# Supersensor.net
KiCad netlist of a schematic drawn in Altium Designer
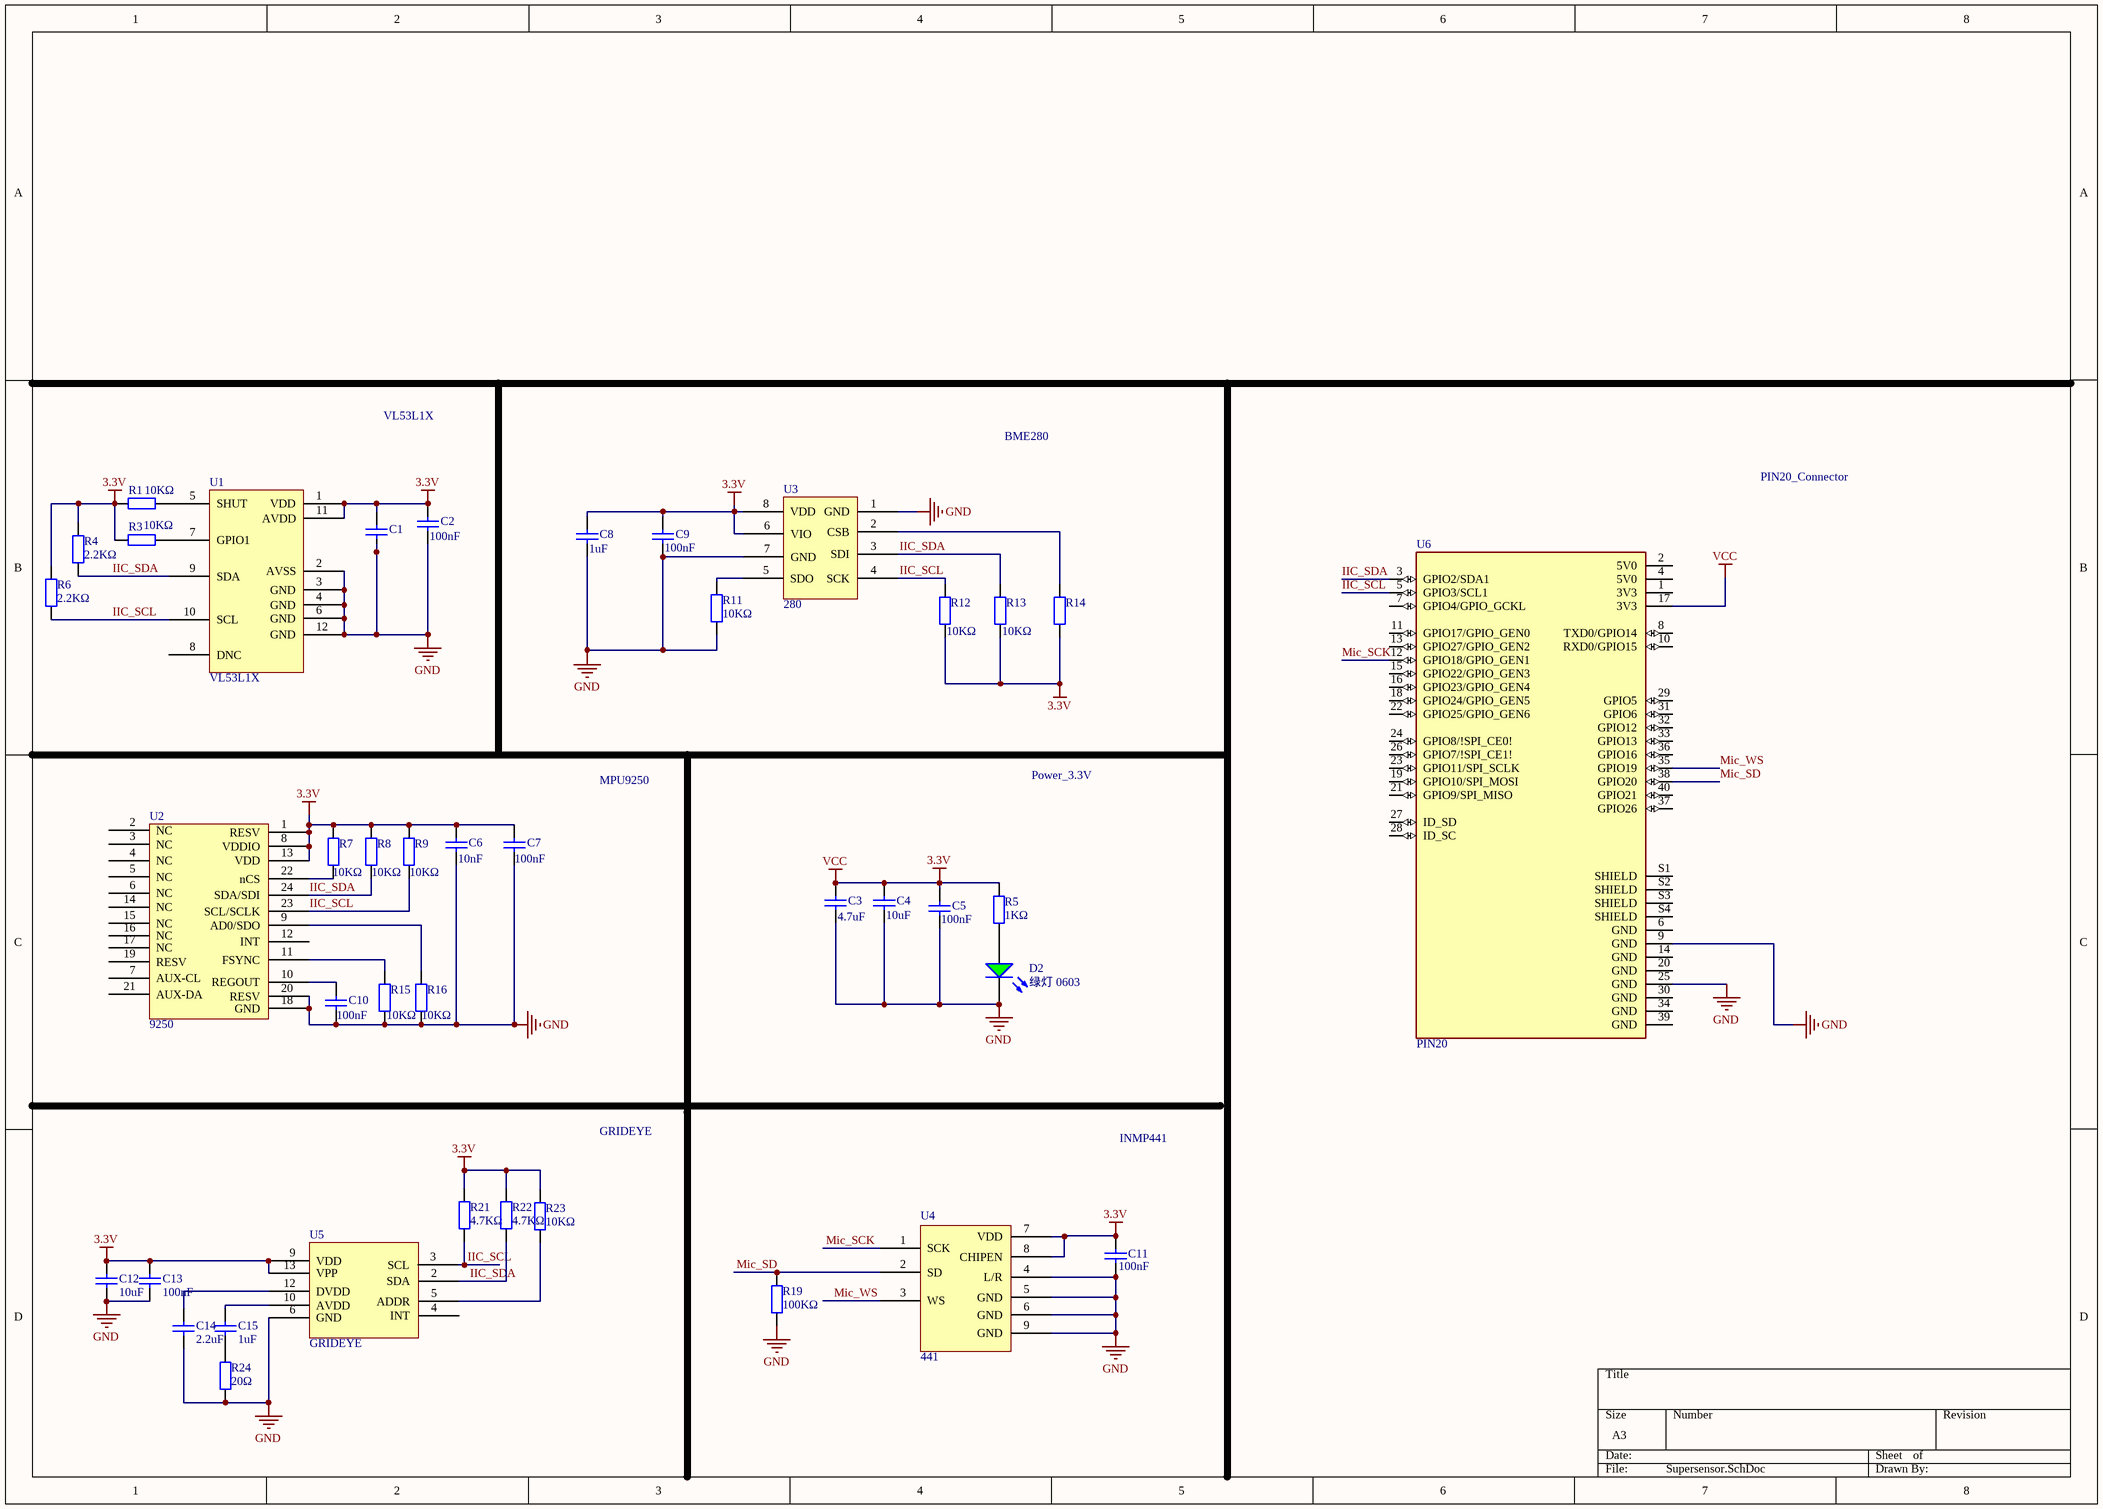
[diagram p0: Supersensor.SchDoc]

(export (version "E")
  (design (tool "Eeschema 10.0.6"))
  (components
    (comp (ref "C1")
      (value "~")
      (footprint "0603_C")
      (description "贴片电容")
      (libsource (lib "Miscellaneous Devices LC") (part "0603 4.7uF (475) 10% 16V"))
    )
    (comp (ref "C2")
      (value "100nF")
      (footprint "0603_C")
      (description "贴片电容")
      (libsource (lib "supersensor") (part "0603 100nF (104) 10% 50V"))
    )
    (comp (ref "C3")
      (value "4.7uF")
      (footprint "0603_C")
      (description "贴片电容")
      (libsource (lib "supersensor") (part "0603 4.7uF (475) 10% 16V"))
    )
    (comp (ref "C4")
      (value "10uF")
      (footprint "0603_C")
      (description "贴片电容")
      (libsource (lib "supersensor") (part "0603 10uF (106) 10% 10V"))
    )
    (comp (ref "C5")
      (value "100nF")
      (footprint "0603_C")
      (description "贴片电容")
      (libsource (lib "supersensor") (part "0603 100nF (104) 10% 50V"))
    )
    (comp (ref "C6")
      (value "10nF")
      (footprint "0603_C")
      (description "贴片电容")
      (libsource (lib "supersensor") (part "0603 10nF (103) 10% 50V"))
    )
    (comp (ref "C7")
      (value "100nF")
      (footprint "0603_C")
      (description "贴片电容")
      (libsource (lib "supersensor") (part "0603 100nF (104) 10% 50V"))
    )
    (comp (ref "C8")
      (value "1uF")
      (footprint "0603_C")
      (description "贴片电容")
      (libsource (lib "supersensor") (part "0603 1uF (105) 10% 50V"))
    )
    (comp (ref "C9")
      (value "100nF")
      (footprint "0603_C")
      (description "贴片电容")
      (libsource (lib "supersensor") (part "0603 100nF (104) 10% 50V"))
    )
    (comp (ref "C10")
      (value "100nF")
      (footprint "0603_C")
      (description "贴片电容")
      (libsource (lib "supersensor") (part "0603 100nF (104) 10% 50V"))
    )
    (comp (ref "C11")
      (value "100nF")
      (footprint "0603_C")
      (description "贴片电容")
      (libsource (lib "supersensor") (part "0603 100nF (104) 10% 50V"))
    )
    (comp (ref "C12")
      (value "10uF")
      (footprint "0603_C")
      (description "贴片电容")
      (libsource (lib "supersensor") (part "0603 10uF (106) 10% 10V"))
    )
    (comp (ref "C13")
      (value "100nF")
      (footprint "0603_C")
      (description "贴片电容")
      (libsource (lib "supersensor") (part "0603 100nF (104) 10% 50V"))
    )
    (comp (ref "C14")
      (value "2.2uF")
      (footprint "0603_C")
      (description "贴片电容")
      (libsource (lib "supersensor") (part "0603 2.2uF (225) 10% 16V"))
    )
    (comp (ref "C15")
      (value "1uF")
      (footprint "0603_C")
      (description "贴片电容")
      (libsource (lib "supersensor") (part "0603 1uF (105) 10% 50V"))
    )
    (comp (ref "D2")
      (value "绿灯 0603")
      (footprint "0603_LED_S1")
      (description "发光二极管")
      (libsource (lib "supersensor") (part "0603 绿灯"))
    )
    (comp (ref "R1")
      (value "10KΩ")
      (footprint "0603_R")
      (description "贴片电阻")
      (libsource (lib "") (part "0603 10KΩ (1002) 1%_1"))
    )
    (comp (ref "R3")
      (value "10KΩ")
      (footprint "0603_R")
      (description "贴片电阻")
      (libsource (lib "") (part "0603 10KΩ (1002) 1%_1"))
    )
    (comp (ref "R4")
      (value "2.2KΩ")
      (footprint "0603_R")
      (description "贴片电阻")
      (libsource (lib "supersensor") (part "0603 2.2KΩ (2201) 1%"))
    )
    (comp (ref "R5")
      (value "1KΩ")
      (footprint "0603_R")
      (description "贴片电阻")
      (libsource (lib "supersensor") (part "0603 1KΩ (1001) 1%"))
    )
    (comp (ref "R6")
      (value "2.2KΩ")
      (footprint "0603_R")
      (description "贴片电阻")
      (libsource (lib "supersensor") (part "0603 2.2KΩ (2201) 1%"))
    )
    (comp (ref "R7")
      (value "10KΩ")
      (footprint "0603_R")
      (description "贴片电阻")
      (libsource (lib "supersensor") (part "0603 10KΩ (1002) 1%"))
    )
    (comp (ref "R8")
      (value "10KΩ")
      (footprint "0603_R")
      (description "贴片电阻")
      (libsource (lib "supersensor") (part "0603 10KΩ (1002) 1%"))
    )
    (comp (ref "R9")
      (value "10KΩ")
      (footprint "0603_R")
      (description "贴片电阻")
      (libsource (lib "supersensor") (part "0603 10KΩ (1002) 1%"))
    )
    (comp (ref "R11")
      (value "10KΩ")
      (footprint "0603_R")
      (description "贴片电阻")
      (libsource (lib "supersensor") (part "0603 10KΩ (1002) 1%"))
    )
    (comp (ref "R12")
      (value "10KΩ")
      (footprint "0603_R")
      (description "贴片电阻")
      (libsource (lib "supersensor") (part "0603 10KΩ (1002) 1%"))
    )
    (comp (ref "R13")
      (value "10KΩ")
      (footprint "0603_R")
      (description "贴片电阻")
      (libsource (lib "supersensor") (part "0603 10KΩ (1002) 1%"))
    )
    (comp (ref "R14")
      (value "~")
      (footprint "0603_R")
      (description "贴片电阻")
      (libsource (lib "Miscellaneous Devices LC") (part "0603 10KΩ (1002) 1%"))
    )
    (comp (ref "R15")
      (value "10KΩ")
      (footprint "0603_R")
      (description "贴片电阻")
      (libsource (lib "supersensor") (part "0603 10KΩ (1002) 1%"))
    )
    (comp (ref "R16")
      (value "10KΩ")
      (footprint "0603_R")
      (description "贴片电阻")
      (libsource (lib "supersensor") (part "0603 10KΩ (1002) 1%"))
    )
    (comp (ref "R19")
      (value "100KΩ")
      (footprint "0603_R")
      (description "贴片电阻")
      (libsource (lib "supersensor") (part "0603 100KΩ (1003) 1%"))
    )
    (comp (ref "R21")
      (value "4.7KΩ")
      (footprint "0603_R")
      (description "贴片电阻")
      (libsource (lib "supersensor") (part "0603 4.7KΩ (4701) 1%"))
    )
    (comp (ref "R22")
      (value "4.7KΩ")
      (footprint "0603_R")
      (description "贴片电阻")
      (libsource (lib "supersensor") (part "0603 4.7KΩ (4701) 1%"))
    )
    (comp (ref "R23")
      (value "10KΩ")
      (footprint "0603_R")
      (description "贴片电阻")
      (libsource (lib "supersensor") (part "0603 10KΩ (1002) 1%"))
    )
    (comp (ref "R24")
      (value "20Ω")
      (footprint "0603_R")
      (description "贴片电阻")
      (libsource (lib "supersensor") (part "0603 20Ω (20R0) 1%"))
    )
    (comp (ref "U1")
      (value "VL53L1X")
      (footprint "VL53L1X")
      (description "IC")
      (libsource (lib "supersensor") (part "VL53L1X"))
    )
    (comp (ref "U2")
      (value "9250")
      (footprint "MPU9250")
      (description "IC")
      (libsource (lib "supersensor") (part "MPU9250"))
    )
    (comp (ref "U3")
      (value "280")
      (footprint "BME280")
      (description "IC")
      (libsource (lib "supersensor") (part "BME280"))
    )
    (comp (ref "U4")
      (value "441")
      (footprint "INMP441")
      (description "IC")
      (libsource (lib "supersensor") (part "INMP441"))
    )
    (comp (ref "U5")
      (value "GRIDEYE")
      (footprint "AMG8833")
      (description "IC")
      (libsource (lib "supersensor") (part "GRIDEYE"))
    )
    (comp (ref "U6")
      (value "PIN20")
      (footprint "PIN20")
      (description "BCM2837B0 Raspberry Pi 3 Model B+ - ARMÂ® CortexÂ®-A53, VideoCore MPU Embedded Evaluation Board")
      (fields (field (name "MP") "RASPBERRY PI 3 MODEL B+") (field (name "MF") "Raspberry Pi"))
      (libsource (lib "supersensor") (part "PIN20"))
    )
  )
  (nets
    (net (code "1") (name "/IIC_SCL") (class "Default")
      (node (ref "R12") (pin "2") (pinfunction "2_2") (pintype "passive"))
      (node (ref "R21") (pin "1") (pinfunction "1_1") (pintype "passive"))
      (node (ref "R6") (pin "2") (pinfunction "2_2") (pintype "passive"))
      (node (ref "R9") (pin "1") (pinfunction "1_1") (pintype "passive"))
      (node (ref "U1") (pin "10") (pinfunction "SCL_10") (pintype "passive"))
      (node (ref "U2") (pin "23") (pinfunction "SCL/SCLK_23") (pintype "passive"))
      (node (ref "U3") (pin "4") (pinfunction "SCK_4") (pintype "passive"))
      (node (ref "U5") (pin "3") (pinfunction "SCL_3") (pintype "passive"))
      (node (ref "U6") (pin "5") (pinfunction "GPIO3/SCL1_5") (pintype "bidirectional"))
    )
    (net (code "2") (name "/IIC_SDA") (class "Default")
      (node (ref "R13") (pin "2") (pinfunction "2_2") (pintype "passive"))
      (node (ref "R22") (pin "1") (pinfunction "1_1") (pintype "passive"))
      (node (ref "R4") (pin "2") (pinfunction "2_2") (pintype "passive"))
      (node (ref "R8") (pin "1") (pinfunction "1_1") (pintype "passive"))
      (node (ref "U1") (pin "9") (pinfunction "SDA_9") (pintype "passive"))
      (node (ref "U2") (pin "24") (pinfunction "SDA/SDI_24") (pintype "passive"))
      (node (ref "U3") (pin "3") (pinfunction "SDI_3") (pintype "passive"))
      (node (ref "U5") (pin "2") (pinfunction "SDA_2") (pintype "passive"))
      (node (ref "U6") (pin "3") (pinfunction "GPIO2/SDA1_3") (pintype "bidirectional"))
    )
    (net (code "3") (name "/Mic_SCK") (class "Default")
      (node (ref "U4") (pin "1") (pinfunction "SCK_1") (pintype "passive"))
      (node (ref "U6") (pin "12") (pinfunction "GPIO18/GPIO_GEN1_12") (pintype "bidirectional"))
    )
    (net (code "4") (name "/Mic_SD") (class "Default")
      (node (ref "R19") (pin "2") (pinfunction "2_2") (pintype "passive"))
      (node (ref "U4") (pin "2") (pinfunction "SD_2") (pintype "passive"))
      (node (ref "U6") (pin "38") (pinfunction "GPIO20_38") (pintype "bidirectional"))
    )
    (net (code "5") (name "/Mic_WS") (class "Default")
      (node (ref "U4") (pin "3") (pinfunction "WS_3") (pintype "passive"))
      (node (ref "U6") (pin "35") (pinfunction "GPIO19_35") (pintype "bidirectional"))
    )
    (net (code "6") (name "3.3V") (class "Default")
      (node (ref "C1") (pin "2") (pinfunction "2_2") (pintype "passive"))
      (node (ref "C11") (pin "2") (pinfunction "2_2") (pintype "passive"))
      (node (ref "C12") (pin "2") (pinfunction "2_2") (pintype "passive"))
      (node (ref "C13") (pin "2") (pinfunction "2_2") (pintype "passive"))
      (node (ref "C2") (pin "2") (pinfunction "2_2") (pintype "passive"))
      (node (ref "C3") (pin "2") (pinfunction "2_2") (pintype "passive"))
      (node (ref "C4") (pin "2") (pinfunction "2_2") (pintype "passive"))
      (node (ref "C5") (pin "2") (pinfunction "2_2") (pintype "passive"))
      (node (ref "C6") (pin "2") (pinfunction "2_2") (pintype "passive"))
      (node (ref "C7") (pin "2") (pinfunction "2_2") (pintype "passive"))
      (node (ref "C8") (pin "2") (pinfunction "2_2") (pintype "passive"))
      (node (ref "C9") (pin "2") (pinfunction "2_2") (pintype "passive"))
      (node (ref "R1") (pin "1") (pinfunction "1_1") (pintype "passive"))
      (node (ref "R12") (pin "1") (pinfunction "1_1") (pintype "passive"))
      (node (ref "R13") (pin "1") (pinfunction "1_1") (pintype "passive"))
      (node (ref "R14") (pin "1") (pinfunction "1_1") (pintype "passive"))
      (node (ref "R21") (pin "2") (pinfunction "2_2") (pintype "passive"))
      (node (ref "R22") (pin "2") (pinfunction "2_2") (pintype "passive"))
      (node (ref "R23") (pin "2") (pinfunction "2_2") (pintype "passive"))
      (node (ref "R3") (pin "1") (pinfunction "1_1") (pintype "passive"))
      (node (ref "R4") (pin "1") (pinfunction "1_1") (pintype "passive"))
      (node (ref "R5") (pin "2") (pinfunction "2_2") (pintype "passive"))
      (node (ref "R6") (pin "1") (pinfunction "1_1") (pintype "passive"))
      (node (ref "R7") (pin "2") (pinfunction "2_2") (pintype "passive"))
      (node (ref "R8") (pin "2") (pinfunction "2_2") (pintype "passive"))
      (node (ref "R9") (pin "2") (pinfunction "2_2") (pintype "passive"))
      (node (ref "U1") (pin "1") (pinfunction "VDD_1") (pintype "power_in"))
      (node (ref "U1") (pin "11") (pinfunction "AVDD_11") (pintype "passive"))
      (node (ref "U2") (pin "1") (pinfunction "RESV_1") (pintype "passive"))
      (node (ref "U2") (pin "13") (pinfunction "VDD_13") (pintype "passive"))
      (node (ref "U2") (pin "8") (pinfunction "VDDIO_8") (pintype "passive"))
      (node (ref "U3") (pin "6") (pinfunction "VIO_6") (pintype "passive"))
      (node (ref "U3") (pin "8") (pinfunction "VDD_8") (pintype "passive"))
      (node (ref "U4") (pin "7") (pinfunction "VDD_7") (pintype "passive"))
      (node (ref "U4") (pin "8") (pinfunction "CHIPEN_8") (pintype "passive"))
      (node (ref "U5") (pin "13") (pinfunction "VPP_13") (pintype "passive"))
      (node (ref "U5") (pin "9") (pinfunction "VDD_9") (pintype "passive"))
      (node (ref "U6") (pin "17") (pinfunction "3V3_17") (pintype "power_in"))
    )
    (net (code "7") (name "GND") (class "Default")
      (node (ref "C1") (pin "1") (pinfunction "1_1") (pintype "passive"))
      (node (ref "C10") (pin "1") (pinfunction "1_1") (pintype "passive"))
      (node (ref "C11") (pin "1") (pinfunction "1_1") (pintype "passive"))
      (node (ref "C12") (pin "1") (pinfunction "1_1") (pintype "passive"))
      (node (ref "C13") (pin "1") (pinfunction "1_1") (pintype "passive"))
      (node (ref "C14") (pin "1") (pinfunction "1_1") (pintype "passive"))
      (node (ref "C2") (pin "1") (pinfunction "1_1") (pintype "passive"))
      (node (ref "C3") (pin "1") (pinfunction "1_1") (pintype "passive"))
      (node (ref "C4") (pin "1") (pinfunction "1_1") (pintype "passive"))
      (node (ref "C5") (pin "1") (pinfunction "1_1") (pintype "passive"))
      (node (ref "C6") (pin "1") (pinfunction "1_1") (pintype "passive"))
      (node (ref "C7") (pin "1") (pinfunction "1_1") (pintype "passive"))
      (node (ref "C8") (pin "1") (pinfunction "1_1") (pintype "passive"))
      (node (ref "C9") (pin "1") (pinfunction "1_1") (pintype "passive"))
      (node (ref "D2") (pin "K") (pinfunction "K_K") (pintype "passive"))
      (node (ref "R11") (pin "1") (pinfunction "1_1") (pintype "passive"))
      (node (ref "R15") (pin "1") (pinfunction "1_1") (pintype "passive"))
      (node (ref "R16") (pin "1") (pinfunction "1_1") (pintype "passive"))
      (node (ref "R19") (pin "1") (pinfunction "1_1") (pintype "passive"))
      (node (ref "R24") (pin "1") (pinfunction "1_1") (pintype "passive"))
      (node (ref "U1") (pin "12") (pinfunction "GND_12") (pintype "passive"))
      (node (ref "U1") (pin "2") (pinfunction "AVSS_2") (pintype "passive"))
      (node (ref "U1") (pin "3") (pinfunction "GND_3") (pintype "passive"))
      (node (ref "U1") (pin "4") (pinfunction "GND_4") (pintype "passive"))
      (node (ref "U1") (pin "6") (pinfunction "GND_6") (pintype "passive"))
      (node (ref "U2") (pin "18") (pinfunction "GND_18") (pintype "passive"))
      (node (ref "U2") (pin "20") (pinfunction "RESV_20") (pintype "passive"))
      (node (ref "U3") (pin "1") (pinfunction "GND_1") (pintype "passive"))
      (node (ref "U3") (pin "7") (pinfunction "GND_7") (pintype "passive"))
      (node (ref "U4") (pin "4") (pinfunction "L/R_4") (pintype "passive"))
      (node (ref "U4") (pin "5") (pinfunction "GND_5") (pintype "passive"))
      (node (ref "U4") (pin "6") (pinfunction "GND_6") (pintype "passive"))
      (node (ref "U4") (pin "9") (pinfunction "GND_9") (pintype "passive"))
      (node (ref "U5") (pin "6") (pinfunction "GND_6") (pintype "passive"))
      (node (ref "U6") (pin "25") (pinfunction "GND_25") (pintype "power_in"))
      (node (ref "U6") (pin "9") (pinfunction "GND_9") (pintype "power_in"))
    )
    (net (code "8") (name "Net-(C15-Pad1)") (class "Default")
      (node (ref "C15") (pin "1") (pinfunction "1_1") (pintype "passive"))
      (node (ref "R24") (pin "2") (pinfunction "2_2") (pintype "passive"))
    )
    (net (code "9") (name "Net-(D2-PadA)") (class "Default")
      (node (ref "D2") (pin "A") (pinfunction "A_A") (pintype "passive"))
      (node (ref "R5") (pin "1") (pinfunction "1_1") (pintype "passive"))
    )
    (net (code "10") (name "Net-(U1-GPIO1)") (class "Default")
      (node (ref "R3") (pin "2") (pinfunction "2_2") (pintype "passive"))
      (node (ref "U1") (pin "7") (pinfunction "GPIO1_7") (pintype "passive"))
    )
    (net (code "11") (name "Net-(U1-SHUT)") (class "Default")
      (node (ref "R1") (pin "2") (pinfunction "2_2") (pintype "passive"))
      (node (ref "U1") (pin "5") (pinfunction "SHUT_5") (pintype "passive"))
    )
    (net (code "12") (name "Net-(U2-AD0{slash}SDO)") (class "Default")
      (node (ref "R16") (pin "2") (pinfunction "2_2") (pintype "passive"))
      (node (ref "U2") (pin "9") (pinfunction "AD0/SDO_9") (pintype "passive"))
    )
    (net (code "13") (name "Net-(U2-FSYNC)") (class "Default")
      (node (ref "R15") (pin "2") (pinfunction "2_2") (pintype "passive"))
      (node (ref "U2") (pin "11") (pinfunction "FSYNC_11") (pintype "passive"))
    )
    (net (code "14") (name "Net-(U2-REGOUT)") (class "Default")
      (node (ref "C10") (pin "2") (pinfunction "2_2") (pintype "passive"))
      (node (ref "U2") (pin "10") (pinfunction "REGOUT_10") (pintype "passive"))
    )
    (net (code "15") (name "Net-(U2-nCS)") (class "Default")
      (node (ref "R7") (pin "1") (pinfunction "1_1") (pintype "passive"))
      (node (ref "U2") (pin "22") (pinfunction "nCS_22") (pintype "passive"))
    )
    (net (code "16") (name "Net-(U3-CSB)") (class "Default")
      (node (ref "R14") (pin "2") (pinfunction "2_2") (pintype "passive"))
      (node (ref "U3") (pin "2") (pinfunction "CSB_2") (pintype "passive"))
    )
    (net (code "17") (name "Net-(U3-SDO)") (class "Default")
      (node (ref "R11") (pin "2") (pinfunction "2_2") (pintype "passive"))
      (node (ref "U3") (pin "5") (pinfunction "SDO_5") (pintype "passive"))
    )
    (net (code "18") (name "Net-(U5-ADDR)") (class "Default")
      (node (ref "R23") (pin "1") (pinfunction "1_1") (pintype "passive"))
      (node (ref "U5") (pin "5") (pinfunction "ADDR_5") (pintype "passive"))
    )
    (net (code "19") (name "Net-(U5-AVDD)") (class "Default")
      (node (ref "C15") (pin "2") (pinfunction "2_2") (pintype "passive"))
      (node (ref "U5") (pin "10") (pinfunction "AVDD_10") (pintype "passive"))
    )
    (net (code "20") (name "Net-(U5-DVDD)") (class "Default")
      (node (ref "C14") (pin "2") (pinfunction "2_2") (pintype "passive"))
      (node (ref "U5") (pin "12") (pinfunction "DVDD_12") (pintype "passive"))
    )
    (net (code "21") (name "unconnected-(U1-DNC-Pad8)") (class "Default")
      (node (ref "U1") (pin "8") (pinfunction "DNC_8") (pintype "passive"))
    )
    (net (code "22") (name "unconnected-(U2-AUX-CL-Pad7)") (class "Default")
      (node (ref "U2") (pin "7") (pinfunction "AUX-CL_7") (pintype "passive"))
    )
    (net (code "23") (name "unconnected-(U2-AUX-DA-Pad21)") (class "Default")
      (node (ref "U2") (pin "21") (pinfunction "AUX-DA_21") (pintype "passive"))
    )
    (net (code "24") (name "unconnected-(U2-INT-Pad12)") (class "Default")
      (node (ref "U2") (pin "12") (pinfunction "INT_12") (pintype "passive"))
    )
    (net (code "25") (name "unconnected-(U2-NC-Pad2)") (class "Default")
      (node (ref "U2") (pin "2") (pinfunction "NC_2") (pintype "passive"))
    )
    (net (code "26") (name "unconnected-(U2-NC-Pad3)") (class "Default")
      (node (ref "U2") (pin "3") (pinfunction "NC_3") (pintype "passive"))
    )
    (net (code "27") (name "unconnected-(U2-NC-Pad4)") (class "Default")
      (node (ref "U2") (pin "4") (pinfunction "NC_4") (pintype "passive"))
    )
    (net (code "28") (name "unconnected-(U2-NC-Pad5)") (class "Default")
      (node (ref "U2") (pin "5") (pinfunction "NC_5") (pintype "passive"))
    )
    (net (code "29") (name "unconnected-(U2-NC-Pad6)") (class "Default")
      (node (ref "U2") (pin "6") (pinfunction "NC_6") (pintype "passive"))
    )
    (net (code "30") (name "unconnected-(U2-NC-Pad14)") (class "Default")
      (node (ref "U2") (pin "14") (pinfunction "NC_14") (pintype "passive"))
    )
    (net (code "31") (name "unconnected-(U2-NC-Pad15)") (class "Default")
      (node (ref "U2") (pin "15") (pinfunction "NC_15") (pintype "passive"))
    )
    (net (code "32") (name "unconnected-(U2-NC-Pad16)") (class "Default")
      (node (ref "U2") (pin "16") (pinfunction "NC_16") (pintype "passive"))
    )
    (net (code "33") (name "unconnected-(U2-NC-Pad17)") (class "Default")
      (node (ref "U2") (pin "17") (pinfunction "NC_17") (pintype "passive"))
    )
    (net (code "34") (name "unconnected-(U2-RESV-Pad19)") (class "Default")
      (node (ref "U2") (pin "19") (pinfunction "RESV_19") (pintype "passive"))
    )
    (net (code "35") (name "unconnected-(U5-INT-Pad4)") (class "Default")
      (node (ref "U5") (pin "4") (pinfunction "INT_4") (pintype "passive"))
    )
    (net (code "36") (name "unconnected-(U6-3V3-Pad1)") (class "Default")
      (node (ref "U6") (pin "1") (pinfunction "3V3_1") (pintype "power_in"))
    )
    (net (code "37") (name "unconnected-(U6-5V0-Pad2)") (class "Default")
      (node (ref "U6") (pin "2") (pinfunction "5V0_2") (pintype "power_in"))
    )
    (net (code "38") (name "unconnected-(U6-5V0-Pad4)") (class "Default")
      (node (ref "U6") (pin "4") (pinfunction "5V0_4") (pintype "power_in"))
    )
    (net (code "39") (name "unconnected-(U6-GND-Pad6)") (class "Default")
      (node (ref "U6") (pin "6") (pinfunction "GND_6") (pintype "power_in"))
    )
    (net (code "40") (name "unconnected-(U6-GND-Pad14)") (class "Default")
      (node (ref "U6") (pin "14") (pinfunction "GND_14") (pintype "power_in"))
    )
    (net (code "41") (name "unconnected-(U6-GND-Pad20)") (class "Default")
      (node (ref "U6") (pin "20") (pinfunction "GND_20") (pintype "power_in"))
    )
    (net (code "42") (name "unconnected-(U6-GND-Pad30)") (class "Default")
      (node (ref "U6") (pin "30") (pinfunction "GND_30") (pintype "power_in"))
    )
    (net (code "43") (name "unconnected-(U6-GND-Pad34)") (class "Default")
      (node (ref "U6") (pin "34") (pinfunction "GND_34") (pintype "power_in"))
    )
    (net (code "44") (name "unconnected-(U6-GND-Pad39)") (class "Default")
      (node (ref "U6") (pin "39") (pinfunction "GND_39") (pintype "power_in"))
    )
    (net (code "45") (name "unconnected-(U6-GPIO4{slash}GPIO_GCKL-Pad7)") (class "Default")
      (node (ref "U6") (pin "7") (pinfunction "GPIO4/GPIO_GCKL_7") (pintype "bidirectional"))
    )
    (net (code "46") (name "unconnected-(U6-GPIO5-Pad29)") (class "Default")
      (node (ref "U6") (pin "29") (pinfunction "GPIO5_29") (pintype "bidirectional"))
    )
    (net (code "47") (name "unconnected-(U6-GPIO6-Pad31)") (class "Default")
      (node (ref "U6") (pin "31") (pinfunction "GPIO6_31") (pintype "bidirectional"))
    )
    (net (code "48") (name "unconnected-(U6-GPIO7{slash}!SPI_CE1!-Pad26)") (class "Default")
      (node (ref "U6") (pin "26") (pinfunction "GPIO7/!SPI_CE1!_26") (pintype "bidirectional"))
    )
    (net (code "49") (name "unconnected-(U6-GPIO8{slash}!SPI_CE0!-Pad24)") (class "Default")
      (node (ref "U6") (pin "24") (pinfunction "GPIO8/!SPI_CE0!_24") (pintype "bidirectional"))
    )
    (net (code "50") (name "unconnected-(U6-GPIO9{slash}SPI_MISO-Pad21)") (class "Default")
      (node (ref "U6") (pin "21") (pinfunction "GPIO9/SPI_MISO_21") (pintype "bidirectional"))
    )
    (net (code "51") (name "unconnected-(U6-GPIO10{slash}SPI_MOSI-Pad19)") (class "Default")
      (node (ref "U6") (pin "19") (pinfunction "GPIO10/SPI_MOSI_19") (pintype "bidirectional"))
    )
    (net (code "52") (name "unconnected-(U6-GPIO11{slash}SPI_SCLK-Pad23)") (class "Default")
      (node (ref "U6") (pin "23") (pinfunction "GPIO11/SPI_SCLK_23") (pintype "bidirectional"))
    )
    (net (code "53") (name "unconnected-(U6-GPIO12-Pad32)") (class "Default")
      (node (ref "U6") (pin "32") (pinfunction "GPIO12_32") (pintype "bidirectional"))
    )
    (net (code "54") (name "unconnected-(U6-GPIO13-Pad33)") (class "Default")
      (node (ref "U6") (pin "33") (pinfunction "GPIO13_33") (pintype "bidirectional"))
    )
    (net (code "55") (name "unconnected-(U6-GPIO16-Pad36)") (class "Default")
      (node (ref "U6") (pin "36") (pinfunction "GPIO16_36") (pintype "bidirectional"))
    )
    (net (code "56") (name "unconnected-(U6-GPIO17{slash}GPIO_GEN0-Pad11)") (class "Default")
      (node (ref "U6") (pin "11") (pinfunction "GPIO17/GPIO_GEN0_11") (pintype "bidirectional"))
    )
    (net (code "57") (name "unconnected-(U6-GPIO21-Pad40)") (class "Default")
      (node (ref "U6") (pin "40") (pinfunction "GPIO21_40") (pintype "bidirectional"))
    )
    (net (code "58") (name "unconnected-(U6-GPIO22{slash}GPIO_GEN3-Pad15)") (class "Default")
      (node (ref "U6") (pin "15") (pinfunction "GPIO22/GPIO_GEN3_15") (pintype "bidirectional"))
    )
    (net (code "59") (name "unconnected-(U6-GPIO23{slash}GPIO_GEN4-Pad16)") (class "Default")
      (node (ref "U6") (pin "16") (pinfunction "GPIO23/GPIO_GEN4_16") (pintype "bidirectional"))
    )
    (net (code "60") (name "unconnected-(U6-GPIO24{slash}GPIO_GEN5-Pad18)") (class "Default")
      (node (ref "U6") (pin "18") (pinfunction "GPIO24/GPIO_GEN5_18") (pintype "bidirectional"))
    )
    (net (code "61") (name "unconnected-(U6-GPIO25{slash}GPIO_GEN6-Pad22)") (class "Default")
      (node (ref "U6") (pin "22") (pinfunction "GPIO25/GPIO_GEN6_22") (pintype "bidirectional"))
    )
    (net (code "62") (name "unconnected-(U6-GPIO26-Pad37)") (class "Default")
      (node (ref "U6") (pin "37") (pinfunction "GPIO26_37") (pintype "bidirectional"))
    )
    (net (code "63") (name "unconnected-(U6-GPIO27{slash}GPIO_GEN2-Pad13)") (class "Default")
      (node (ref "U6") (pin "13") (pinfunction "GPIO27/GPIO_GEN2_13") (pintype "bidirectional"))
    )
    (net (code "64") (name "unconnected-(U6-ID_SC-Pad28)") (class "Default")
      (node (ref "U6") (pin "28") (pinfunction "ID_SC_28") (pintype "bidirectional"))
    )
    (net (code "65") (name "unconnected-(U6-ID_SD-Pad27)") (class "Default")
      (node (ref "U6") (pin "27") (pinfunction "ID_SD_27") (pintype "bidirectional"))
    )
    (net (code "66") (name "unconnected-(U6-RXD0{slash}GPIO15-Pad10)") (class "Default")
      (node (ref "U6") (pin "10") (pinfunction "RXD0/GPIO15_10") (pintype "bidirectional"))
    )
    (net (code "67") (name "unconnected-(U6-SHIELD-PadS1)") (class "Default")
      (node (ref "U6") (pin "S1") (pinfunction "SHIELD_S1") (pintype "power_in"))
    )
    (net (code "68") (name "unconnected-(U6-SHIELD-PadS2)") (class "Default")
      (node (ref "U6") (pin "S2") (pinfunction "SHIELD_S2") (pintype "power_in"))
    )
    (net (code "69") (name "unconnected-(U6-SHIELD-PadS3)") (class "Default")
      (node (ref "U6") (pin "S3") (pinfunction "SHIELD_S3") (pintype "power_in"))
    )
    (net (code "70") (name "unconnected-(U6-SHIELD-PadS4)") (class "Default")
      (node (ref "U6") (pin "S4") (pinfunction "SHIELD_S4") (pintype "power_in"))
    )
    (net (code "71") (name "unconnected-(U6-TXD0{slash}GPIO14-Pad8)") (class "Default")
      (node (ref "U6") (pin "8") (pinfunction "TXD0/GPIO14_8") (pintype "bidirectional"))
    )
  )
)
